# BalEv_STM_v1_0.net
KiCad netlist of a schematic drawn in Altium Designer
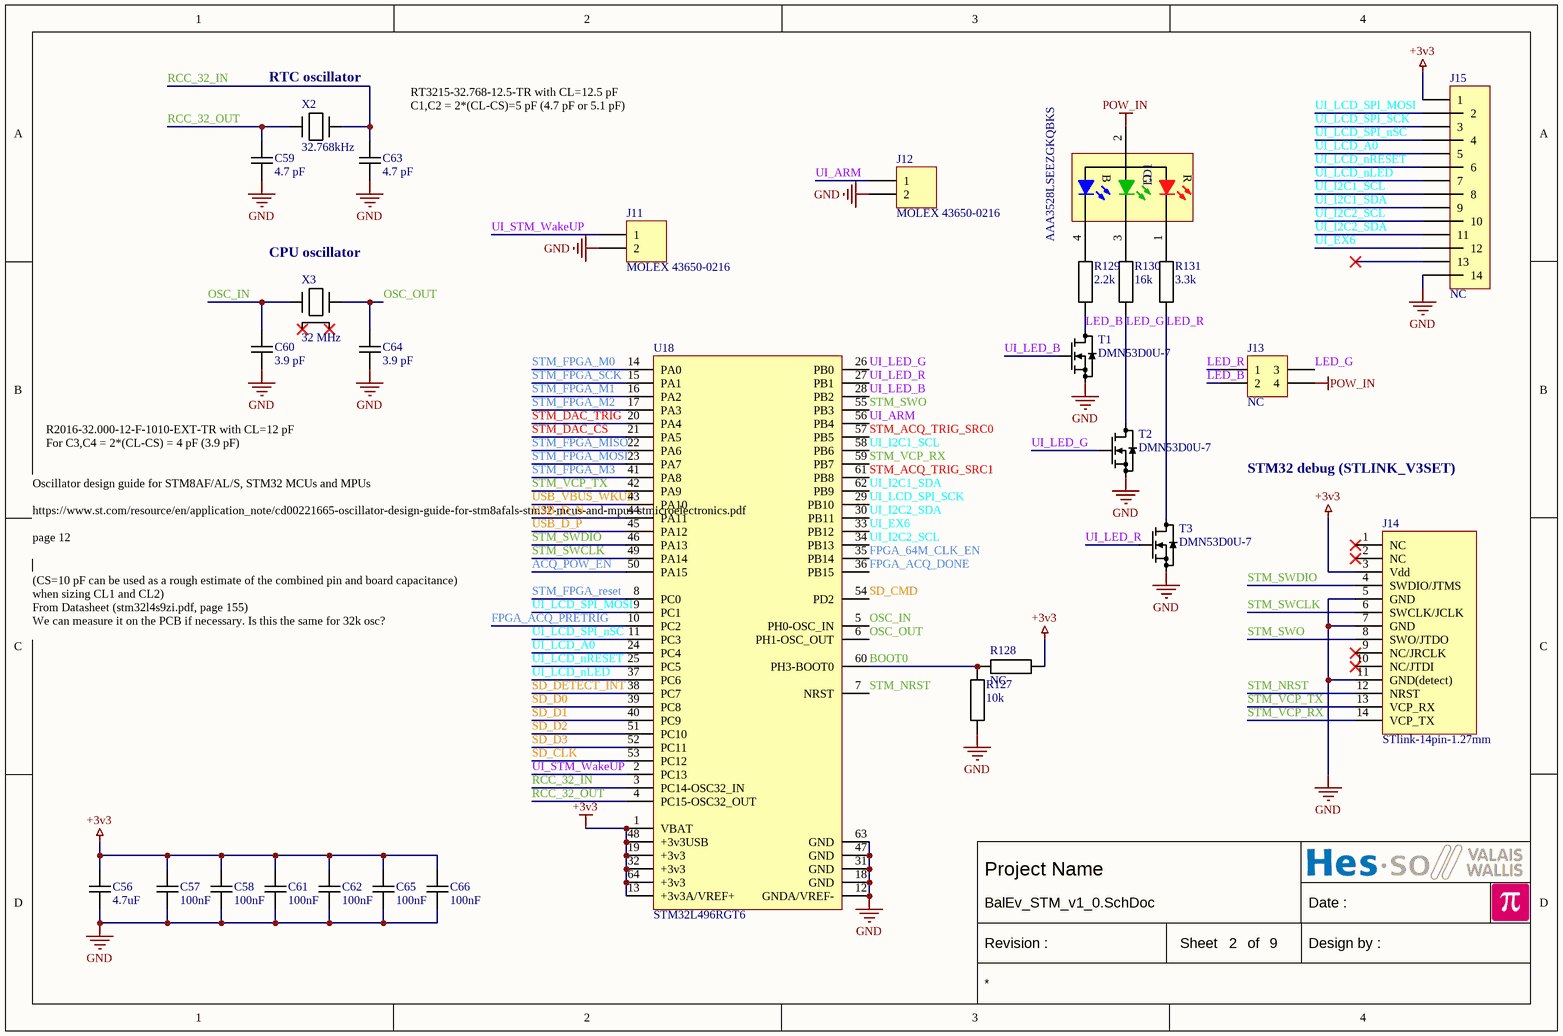
[diagram p0: BalEv_STM_v1_0.SchDoc]

(export (version "E")
  (design (tool "Eeschema 10.0.6"))
  (components
    (comp (ref "C56")
      (value "4.7uF")
      (footprint "CAPACITOR 1005 REFLOW")
      (description "Capacitor")
      (libsource (lib "Capacitor") (part "Capacitor"))
    )
    (comp (ref "C57")
      (value "100nF")
      (footprint "CAPACITOR 1005 REFLOW")
      (description "Capacitor")
      (libsource (lib "Capacitor") (part "Capacitor"))
    )
    (comp (ref "C58")
      (value "100nF")
      (footprint "CAPACITOR 1005 REFLOW")
      (description "Capacitor")
      (libsource (lib "Capacitor") (part "Capacitor"))
    )
    (comp (ref "C59")
      (value "4.7 pF")
      (footprint "CAPACITOR 1005 REFLOW")
      (description "Capacitor")
      (libsource (lib "Capacitor") (part "Capacitor"))
    )
    (comp (ref "C60")
      (value "3.9 pF")
      (footprint "CAPACITOR 1005 REFLOW")
      (description "Capacitor")
      (libsource (lib "Capacitor") (part "Capacitor"))
    )
    (comp (ref "C61")
      (value "100nF")
      (footprint "CAPACITOR 1005 REFLOW")
      (description "Capacitor")
      (libsource (lib "Capacitor") (part "Capacitor"))
    )
    (comp (ref "C62")
      (value "100nF")
      (footprint "CAPACITOR 1005 REFLOW")
      (description "Capacitor")
      (libsource (lib "Capacitor") (part "Capacitor"))
    )
    (comp (ref "C63")
      (value "4.7 pF")
      (footprint "CAPACITOR 1005 REFLOW")
      (description "Capacitor")
      (libsource (lib "Capacitor") (part "Capacitor"))
    )
    (comp (ref "C64")
      (value "3.9 pF")
      (footprint "CAPACITOR 1005 REFLOW")
      (description "Capacitor")
      (libsource (lib "Capacitor") (part "Capacitor"))
    )
    (comp (ref "C65")
      (value "100nF")
      (footprint "CAPACITOR 1005 REFLOW")
      (description "Capacitor")
      (libsource (lib "Capacitor") (part "Capacitor"))
    )
    (comp (ref "C66")
      (value "100nF")
      (footprint "CAPACITOR 1005 REFLOW")
      (description "Capacitor")
      (libsource (lib "Capacitor") (part "Capacitor"))
    )
    (comp (ref "J11")
      (value "MOLEX 43650-0216")
      (footprint "MOLEX 43650-0216")
      (description "Micro-Fit 3.0 Vertical Header, 3.00mm Pitch, Single Row, 2 Circuits")
      (libsource (lib "Connector") (part "MOLEX 43650-0216"))
    )
    (comp (ref "J12")
      (value "MOLEX 43650-0216")
      (footprint "MOLEX 43650-0216")
      (description "Micro-Fit 3.0 Vertical Header, 3.00mm Pitch, Single Row, 2 Circuits")
      (libsource (lib "Connector") (part "MOLEX 43650-0216"))
    )
    (comp (ref "J13")
      (value "NC")
      (footprint "MOLEX 43045-0412")
      (description "MOLEX 43045-0412")
      (libsource (lib "Connector") (part "MOLEX 43045-0412"))
    )
    (comp (ref "J14")
      (value "STlink-14pin-1.27mm")
      (footprint "SHF-107-01-X-X-TH")
      (libsource (lib "Connector") (part "STlink-14pin-1.27mm"))
    )
    (comp (ref "J15")
      (value "NC")
      (footprint "FlatCable2x7 2MM Straight TH FCI 98414-G06-14ULF")
      (description "FlatCable2x7")
      (libsource (lib "Connector") (part "FlatCable2x7"))
    )
    (comp (ref "LD1")
      (value "AAA3528LSEEZGKQBKS")
      (footprint "LED Kingbright AAA3528LSEEZGKQBKS")
      (description "3.5x2.8mm SURFACE MOUNT LED LAMP")
      (libsource (lib "Diode") (part "LED Kingbright AAA3528LSEEZGKQBKS"))
    )
    (comp (ref "R127")
      (value "10k")
      (footprint "RESISTOR 1005 REFLOW")
      (description "Resistor")
      (libsource (lib "Resistor") (part "Resistor"))
    )
    (comp (ref "R128")
      (value "NC")
      (footprint "RESISTOR 1005 REFLOW")
      (description "Resistor")
      (libsource (lib "Resistor") (part "Resistor"))
    )
    (comp (ref "R129")
      (value "2.2k")
      (footprint "RESISTOR 1005 REFLOW")
      (description "Resistor")
      (libsource (lib "Resistor") (part "Resistor"))
    )
    (comp (ref "R130")
      (value "16k")
      (footprint "RESISTOR 1005 REFLOW")
      (description "Resistor")
      (libsource (lib "Resistor") (part "Resistor"))
    )
    (comp (ref "R131")
      (value "3.3k")
      (footprint "RESISTOR 1005 REFLOW")
      (description "Resistor")
      (libsource (lib "Resistor") (part "Resistor"))
    )
    (comp (ref "T1")
      (value "DMN53D0U-7")
      (footprint "SOT23 P0.95 C1.6x3.0 H1.3")
      (description "Generic MOS-N")
      (libsource (lib "Transistor") (part "MOS-N SOT23 G-S-D"))
    )
    (comp (ref "T2")
      (value "DMN53D0U-7")
      (footprint "SOT23 P0.95 C1.6x3.0 H1.3")
      (description "Generic MOS-N")
      (libsource (lib "Transistor") (part "MOS-N SOT23 G-S-D"))
    )
    (comp (ref "T3")
      (value "DMN53D0U-7")
      (footprint "SOT23 P0.95 C1.6x3.0 H1.3")
      (description "Generic MOS-N")
      (libsource (lib "Transistor") (part "MOS-N SOT23 G-S-D"))
    )
    (comp (ref "U18")
      (value "STM32L496RGT6")
      (footprint "LQFP64 P0.5 C10.0x10.0 H1.6")
      (libsource (lib "Processor") (part "STM32L4X6R_T"))
    )
    (comp (ref "X2")
      (value "32.768kHz")
      (footprint "Crystal C3.2x1.5 Abracon ABS07")
      (description "RT3215-32.768-12.5-TR")
      (libsource (lib "Oscillator") (part "Crystal C3.2x1.5 Abracon ABS07"))
    )
    (comp (ref "X3")
      (value "32 MHz")
      (footprint "Crystal C2.0x1.6 Abracon ABM11W")
      (description "R2016-32.000-12-F-1010-EXT-TR")
      (libsource (lib "Oscillator") (part "Crystal C2.0x1.6 Abracon ABM11W"))
    )
  )
  (nets
    (net (code "1") (name "+3v3") (class "Default")
      (node (ref "C56") (pin "2") (pinfunction "2_2") (pintype "passive"))
      (node (ref "C57") (pin "2") (pinfunction "2_2") (pintype "passive"))
      (node (ref "C58") (pin "2") (pinfunction "2_2") (pintype "passive"))
      (node (ref "C61") (pin "2") (pinfunction "2_2") (pintype "passive"))
      (node (ref "C62") (pin "2") (pinfunction "2_2") (pintype "passive"))
      (node (ref "C65") (pin "2") (pinfunction "2_2") (pintype "passive"))
      (node (ref "C66") (pin "2") (pinfunction "2_2") (pintype "passive"))
      (node (ref "J14") (pin "3") (pinfunction "Vdd_3") (pintype "passive"))
      (node (ref "J15") (pin "1") (pinfunction "1_1") (pintype "passive"))
      (node (ref "R128") (pin "1") (pinfunction "1_1") (pintype "passive"))
      (node (ref "U18") (pin "1") (pinfunction "VBAT_1") (pintype "passive"))
      (node (ref "U18") (pin "13") (pinfunction "+3v3A/VREF+_13") (pintype "passive"))
      (node (ref "U18") (pin "19") (pinfunction "+3v3_19") (pintype "passive"))
      (node (ref "U18") (pin "32") (pinfunction "+3v3_32") (pintype "passive"))
      (node (ref "U18") (pin "48") (pinfunction "+3v3USB_48") (pintype "passive"))
      (node (ref "U18") (pin "64") (pinfunction "+3v3_64") (pintype "passive"))
    )
    (net (code "2") (name "/ACQ_POW_EN") (class "Default")
      (node (ref "U18") (pin "50") (pinfunction "PA15_50") (pintype "passive"))
    )
    (net (code "3") (name "/BOOT0") (class "Default")
      (node (ref "R127") (pin "1") (pinfunction "1_1") (pintype "passive"))
      (node (ref "R128") (pin "2") (pinfunction "2_2") (pintype "passive"))
      (node (ref "U18") (pin "60") (pinfunction "PH3-BOOT0_60") (pintype "passive"))
    )
    (net (code "4") (name "/FPGA_64M_CLK_EN") (class "Default")
      (node (ref "U18") (pin "35") (pinfunction "PB14_35") (pintype "passive"))
    )
    (net (code "5") (name "/FPGA_ACQ_DONE") (class "Default")
      (node (ref "U18") (pin "36") (pinfunction "PB15_36") (pintype "passive"))
    )
    (net (code "6") (name "/FPGA_ACQ_PRETRIG") (class "Default")
      (node (ref "U18") (pin "10") (pinfunction "PC2_10") (pintype "passive"))
    )
    (net (code "7") (name "/LED_B") (class "Default")
      (node (ref "J13") (pin "2") (pinfunction "2_2") (pintype "passive"))
      (node (ref "R129") (pin "2") (pinfunction "2_2") (pintype "passive"))
      (node (ref "T1") (pin "3") (pinfunction "D_3") (pintype "passive"))
    )
    (net (code "8") (name "/LED_G") (class "Default")
      (node (ref "J13") (pin "3") (pinfunction "3_3") (pintype "passive"))
      (node (ref "R130") (pin "2") (pinfunction "2_2") (pintype "passive"))
      (node (ref "T2") (pin "3") (pinfunction "D_3") (pintype "passive"))
    )
    (net (code "9") (name "/LED_R") (class "Default")
      (node (ref "J13") (pin "1") (pinfunction "1_1") (pintype "passive"))
      (node (ref "R131") (pin "2") (pinfunction "2_2") (pintype "passive"))
      (node (ref "T3") (pin "3") (pinfunction "D_3") (pintype "passive"))
    )
    (net (code "10") (name "/OSC_IN") (class "Default")
      (node (ref "C60") (pin "2") (pinfunction "2_2") (pintype "passive"))
      (node (ref "U18") (pin "5") (pinfunction "PH0-OSC_IN_5") (pintype "passive"))
      (node (ref "X3") (pin "1") (pinfunction "1_1") (pintype "passive"))
    )
    (net (code "11") (name "/OSC_OUT") (class "Default")
      (node (ref "C64") (pin "2") (pinfunction "2_2") (pintype "passive"))
      (node (ref "U18") (pin "6") (pinfunction "PH1-OSC_OUT_6") (pintype "passive"))
      (node (ref "X3") (pin "3") (pinfunction "3_3") (pintype "passive"))
    )
    (net (code "12") (name "/RCC_32_IN") (class "Default")
      (node (ref "C63") (pin "2") (pinfunction "2_2") (pintype "passive"))
      (node (ref "U18") (pin "3") (pinfunction "PC14-OSC32_IN_3") (pintype "passive"))
      (node (ref "X2") (pin "2") (pinfunction "2_2") (pintype "passive"))
    )
    (net (code "13") (name "/RCC_32_OUT") (class "Default")
      (node (ref "C59") (pin "2") (pinfunction "2_2") (pintype "passive"))
      (node (ref "U18") (pin "4") (pinfunction "PC15-OSC32_OUT_4") (pintype "passive"))
      (node (ref "X2") (pin "1") (pinfunction "1_1") (pintype "passive"))
    )
    (net (code "14") (name "/SD_CLK") (class "Default")
      (node (ref "U18") (pin "53") (pinfunction "PC12_53") (pintype "passive"))
    )
    (net (code "15") (name "/SD_CMD") (class "Default")
      (node (ref "U18") (pin "54") (pinfunction "PD2_54") (pintype "passive"))
    )
    (net (code "16") (name "/SD_D0") (class "Default")
      (node (ref "U18") (pin "39") (pinfunction "PC8_39") (pintype "passive"))
    )
    (net (code "17") (name "/SD_D1") (class "Default")
      (node (ref "U18") (pin "40") (pinfunction "PC9_40") (pintype "passive"))
    )
    (net (code "18") (name "/SD_D2") (class "Default")
      (node (ref "U18") (pin "51") (pinfunction "PC10_51") (pintype "passive"))
    )
    (net (code "19") (name "/SD_D3") (class "Default")
      (node (ref "U18") (pin "52") (pinfunction "PC11_52") (pintype "passive"))
    )
    (net (code "20") (name "/SD_DETECT_INT") (class "Default")
      (node (ref "U18") (pin "38") (pinfunction "PC7_38") (pintype "passive"))
    )
    (net (code "21") (name "/STM_ACQ_TRIG_SRC0") (class "Default")
      (node (ref "U18") (pin "57") (pinfunction "PB5_57") (pintype "passive"))
    )
    (net (code "22") (name "/STM_ACQ_TRIG_SRC1") (class "Default")
      (node (ref "U18") (pin "61") (pinfunction "PB8_61") (pintype "passive"))
    )
    (net (code "23") (name "/STM_DAC_CS") (class "Default")
      (node (ref "U18") (pin "21") (pinfunction "PA5_21") (pintype "passive"))
    )
    (net (code "24") (name "/STM_DAC_TRIG") (class "Default")
      (node (ref "U18") (pin "20") (pinfunction "PA4_20") (pintype "passive"))
    )
    (net (code "25") (name "/STM_FPGA_M0") (class "Default")
      (node (ref "U18") (pin "14") (pinfunction "PA0_14") (pintype "passive"))
    )
    (net (code "26") (name "/STM_FPGA_M1") (class "Default")
      (node (ref "U18") (pin "16") (pinfunction "PA2_16") (pintype "passive"))
    )
    (net (code "27") (name "/STM_FPGA_M2") (class "Default")
      (node (ref "U18") (pin "17") (pinfunction "PA3_17") (pintype "passive"))
    )
    (net (code "28") (name "/STM_FPGA_M3") (class "Default")
      (node (ref "U18") (pin "41") (pinfunction "PA8_41") (pintype "passive"))
    )
    (net (code "29") (name "/STM_FPGA_MISO") (class "Default")
      (node (ref "U18") (pin "22") (pinfunction "PA6_22") (pintype "passive"))
    )
    (net (code "30") (name "/STM_FPGA_MOSI") (class "Default")
      (node (ref "U18") (pin "23") (pinfunction "PA7_23") (pintype "passive"))
    )
    (net (code "31") (name "/STM_FPGA_SCK") (class "Default")
      (node (ref "U18") (pin "15") (pinfunction "PA1_15") (pintype "passive"))
    )
    (net (code "32") (name "/STM_FPGA_reset") (class "Default")
      (node (ref "U18") (pin "8") (pinfunction "PC0_8") (pintype "passive"))
    )
    (net (code "33") (name "/STM_NRST") (class "Default")
      (node (ref "J14") (pin "12") (pinfunction "NRST_12") (pintype "passive"))
      (node (ref "U18") (pin "7") (pinfunction "NRST_7") (pintype "passive"))
    )
    (net (code "34") (name "/STM_SWCLK") (class "Default")
      (node (ref "J14") (pin "6") (pinfunction "SWCLK/JCLK_6") (pintype "passive"))
      (node (ref "U18") (pin "49") (pinfunction "PA14_49") (pintype "passive"))
    )
    (net (code "35") (name "/STM_SWDIO") (class "Default")
      (node (ref "J14") (pin "4") (pinfunction "SWDIO/JTMS_4") (pintype "passive"))
      (node (ref "U18") (pin "46") (pinfunction "PA13_46") (pintype "passive"))
    )
    (net (code "36") (name "/STM_SWO") (class "Default")
      (node (ref "J14") (pin "8") (pinfunction "SWO/JTDO_8") (pintype "passive"))
      (node (ref "U18") (pin "55") (pinfunction "PB3_55") (pintype "passive"))
    )
    (net (code "37") (name "/STM_VCP_RX") (class "Default")
      (node (ref "J14") (pin "14") (pinfunction "VCP_TX_14") (pintype "passive"))
      (node (ref "U18") (pin "59") (pinfunction "PB7_59") (pintype "passive"))
    )
    (net (code "38") (name "/STM_VCP_TX") (class "Default")
      (node (ref "J14") (pin "13") (pinfunction "VCP_RX_13") (pintype "passive"))
      (node (ref "U18") (pin "42") (pinfunction "PA9_42") (pintype "passive"))
    )
    (net (code "39") (name "/UI_ARM") (class "Default")
      (node (ref "J12") (pin "1") (pinfunction "1_1") (pintype "passive"))
      (node (ref "U18") (pin "56") (pinfunction "PB4_56") (pintype "passive"))
    )
    (net (code "40") (name "/UI_EX6") (class "Default")
      (node (ref "J15") (pin "12") (pinfunction "12_12") (pintype "passive"))
      (node (ref "U18") (pin "33") (pinfunction "PB12_33") (pintype "passive"))
    )
    (net (code "41") (name "/UI_I2C1_SCL") (class "Default")
      (node (ref "J15") (pin "8") (pinfunction "8_8") (pintype "passive"))
      (node (ref "U18") (pin "58") (pinfunction "PB6_58") (pintype "passive"))
    )
    (net (code "42") (name "/UI_I2C1_SDA") (class "Default")
      (node (ref "J15") (pin "9") (pinfunction "9_9") (pintype "passive"))
      (node (ref "U18") (pin "62") (pinfunction "PB9_62") (pintype "passive"))
    )
    (net (code "43") (name "/UI_I2C2_SCL") (class "Default")
      (node (ref "J15") (pin "10") (pinfunction "10_10") (pintype "passive"))
      (node (ref "U18") (pin "34") (pinfunction "PB13_34") (pintype "passive"))
    )
    (net (code "44") (name "/UI_I2C2_SDA") (class "Default")
      (node (ref "J15") (pin "11") (pinfunction "11_11") (pintype "passive"))
      (node (ref "U18") (pin "30") (pinfunction "PB11_30") (pintype "passive"))
    )
    (net (code "45") (name "/UI_LCD_A0") (class "Default")
      (node (ref "J15") (pin "5") (pinfunction "5_5") (pintype "passive"))
      (node (ref "U18") (pin "24") (pinfunction "PC4_24") (pintype "passive"))
    )
    (net (code "46") (name "/UI_LCD_SPI_MOSI") (class "Default")
      (node (ref "J15") (pin "2") (pinfunction "2_2") (pintype "passive"))
      (node (ref "U18") (pin "9") (pinfunction "PC1_9") (pintype "passive"))
    )
    (net (code "47") (name "/UI_LCD_SPI_SCK") (class "Default")
      (node (ref "J15") (pin "3") (pinfunction "3_3") (pintype "passive"))
      (node (ref "U18") (pin "29") (pinfunction "PB10_29") (pintype "passive"))
    )
    (net (code "48") (name "/UI_LCD_SPI_nSC") (class "Default")
      (node (ref "J15") (pin "4") (pinfunction "4_4") (pintype "passive"))
      (node (ref "U18") (pin "11") (pinfunction "PC3_11") (pintype "passive"))
    )
    (net (code "49") (name "/UI_LCD_nLED") (class "Default")
      (node (ref "J15") (pin "7") (pinfunction "7_7") (pintype "passive"))
      (node (ref "U18") (pin "37") (pinfunction "PC6_37") (pintype "passive"))
    )
    (net (code "50") (name "/UI_LCD_nRESET") (class "Default")
      (node (ref "J15") (pin "6") (pinfunction "6_6") (pintype "passive"))
      (node (ref "U18") (pin "25") (pinfunction "PC5_25") (pintype "passive"))
    )
    (net (code "51") (name "/UI_LED_B") (class "Default")
      (node (ref "T1") (pin "1") (pinfunction "G_1") (pintype "passive"))
      (node (ref "U18") (pin "28") (pinfunction "PB2_28") (pintype "passive"))
    )
    (net (code "52") (name "/UI_LED_G") (class "Default")
      (node (ref "T2") (pin "1") (pinfunction "G_1") (pintype "passive"))
      (node (ref "U18") (pin "26") (pinfunction "PB0_26") (pintype "passive"))
    )
    (net (code "53") (name "/UI_LED_R") (class "Default")
      (node (ref "T3") (pin "1") (pinfunction "G_1") (pintype "passive"))
      (node (ref "U18") (pin "27") (pinfunction "PB1_27") (pintype "passive"))
    )
    (net (code "54") (name "/UI_STM_WakeUP") (class "Default")
      (node (ref "J11") (pin "1") (pinfunction "1_1") (pintype "passive"))
      (node (ref "U18") (pin "2") (pinfunction "PC13_2") (pintype "passive"))
    )
    (net (code "55") (name "/USB_D_N") (class "Default")
      (node (ref "U18") (pin "44") (pinfunction "PA11_44") (pintype "passive"))
    )
    (net (code "56") (name "/USB_D_P") (class "Default")
      (node (ref "U18") (pin "45") (pinfunction "PA12_45") (pintype "passive"))
    )
    (net (code "57") (name "/USB_VBUS_WKUP") (class "Default")
      (node (ref "U18") (pin "43") (pinfunction "PA10_43") (pintype "passive"))
    )
    (net (code "58") (name "GND") (class "Default")
      (node (ref "C56") (pin "1") (pinfunction "1_1") (pintype "passive"))
      (node (ref "C57") (pin "1") (pinfunction "1_1") (pintype "passive"))
      (node (ref "C58") (pin "1") (pinfunction "1_1") (pintype "passive"))
      (node (ref "C59") (pin "1") (pinfunction "1_1") (pintype "passive"))
      (node (ref "C60") (pin "1") (pinfunction "1_1") (pintype "passive"))
      (node (ref "C61") (pin "1") (pinfunction "1_1") (pintype "passive"))
      (node (ref "C62") (pin "1") (pinfunction "1_1") (pintype "passive"))
      (node (ref "C63") (pin "1") (pinfunction "1_1") (pintype "passive"))
      (node (ref "C64") (pin "1") (pinfunction "1_1") (pintype "passive"))
      (node (ref "C65") (pin "1") (pinfunction "1_1") (pintype "passive"))
      (node (ref "C66") (pin "1") (pinfunction "1_1") (pintype "passive"))
      (node (ref "J11") (pin "2") (pinfunction "2_2") (pintype "passive"))
      (node (ref "J12") (pin "2") (pinfunction "2_2") (pintype "passive"))
      (node (ref "J14") (pin "11") (pinfunction "GND(detect)_11") (pintype "passive"))
      (node (ref "J14") (pin "5") (pinfunction "GND_5") (pintype "passive"))
      (node (ref "J14") (pin "7") (pinfunction "GND_7") (pintype "passive"))
      (node (ref "J15") (pin "14") (pinfunction "14_14") (pintype "passive"))
      (node (ref "R127") (pin "2") (pinfunction "2_2") (pintype "passive"))
      (node (ref "T1") (pin "2") (pinfunction "S_2") (pintype "passive"))
      (node (ref "T2") (pin "2") (pinfunction "S_2") (pintype "passive"))
      (node (ref "T3") (pin "2") (pinfunction "S_2") (pintype "passive"))
      (node (ref "U18") (pin "12") (pinfunction "GNDA/VREF-_12") (pintype "passive"))
      (node (ref "U18") (pin "18") (pinfunction "GND_18") (pintype "passive"))
      (node (ref "U18") (pin "31") (pinfunction "GND_31") (pintype "passive"))
      (node (ref "U18") (pin "47") (pinfunction "GND_47") (pintype "passive"))
      (node (ref "U18") (pin "63") (pinfunction "GND_63") (pintype "passive"))
    )
    (net (code "59") (name "Net-(LD1-B)") (class "Default")
      (node (ref "LD1") (pin "4") (pinfunction "B_4") (pintype "passive"))
      (node (ref "R129") (pin "1") (pinfunction "1_1") (pintype "passive"))
    )
    (net (code "60") (name "Net-(LD1-G)") (class "Default")
      (node (ref "LD1") (pin "3") (pinfunction "G_3") (pintype "passive"))
      (node (ref "R130") (pin "1") (pinfunction "1_1") (pintype "passive"))
    )
    (net (code "61") (name "Net-(LD1-R)") (class "Default")
      (node (ref "LD1") (pin "1") (pinfunction "R_1") (pintype "passive"))
      (node (ref "R131") (pin "1") (pinfunction "1_1") (pintype "passive"))
    )
    (net (code "62") (name "POW_IN") (class "Default")
      (node (ref "J13") (pin "4") (pinfunction "4_4") (pintype "passive"))
      (node (ref "LD1") (pin "2") (pinfunction "A_2") (pintype "passive"))
    )
    (net (code "63") (name "unconnected-(J14-NC-Pad1)") (class "Default")
      (node (ref "J14") (pin "1") (pinfunction "NC_1") (pintype "passive+no_connect"))
    )
    (net (code "64") (name "unconnected-(J14-NC-Pad2)") (class "Default")
      (node (ref "J14") (pin "2") (pinfunction "NC_2") (pintype "passive+no_connect"))
    )
    (net (code "65") (name "unconnected-(J14-NC{slash}JRCLK-Pad9)") (class "Default")
      (node (ref "J14") (pin "9") (pinfunction "NC/JRCLK_9") (pintype "passive+no_connect"))
    )
    (net (code "66") (name "unconnected-(J14-NC{slash}JTDI-Pad10)") (class "Default")
      (node (ref "J14") (pin "10") (pinfunction "NC/JTDI_10") (pintype "passive+no_connect"))
    )
    (net (code "67") (name "unconnected-(J15-Pad13)") (class "Default")
      (node (ref "J15") (pin "13") (pinfunction "13_13") (pintype "passive+no_connect"))
    )
    (net (code "68") (name "unconnected-(X3-Pad2)") (class "Default")
      (node (ref "X3") (pin "2") (pinfunction "2_2") (pintype "passive+no_connect"))
    )
    (net (code "69") (name "unconnected-(X3-Pad4)") (class "Default")
      (node (ref "X3") (pin "4") (pinfunction "4_4") (pintype "passive+no_connect"))
    )
  )
)
